# CocoMEMJr_v1_00.net
KiCad netlist of a schematic drawn in EAGLE
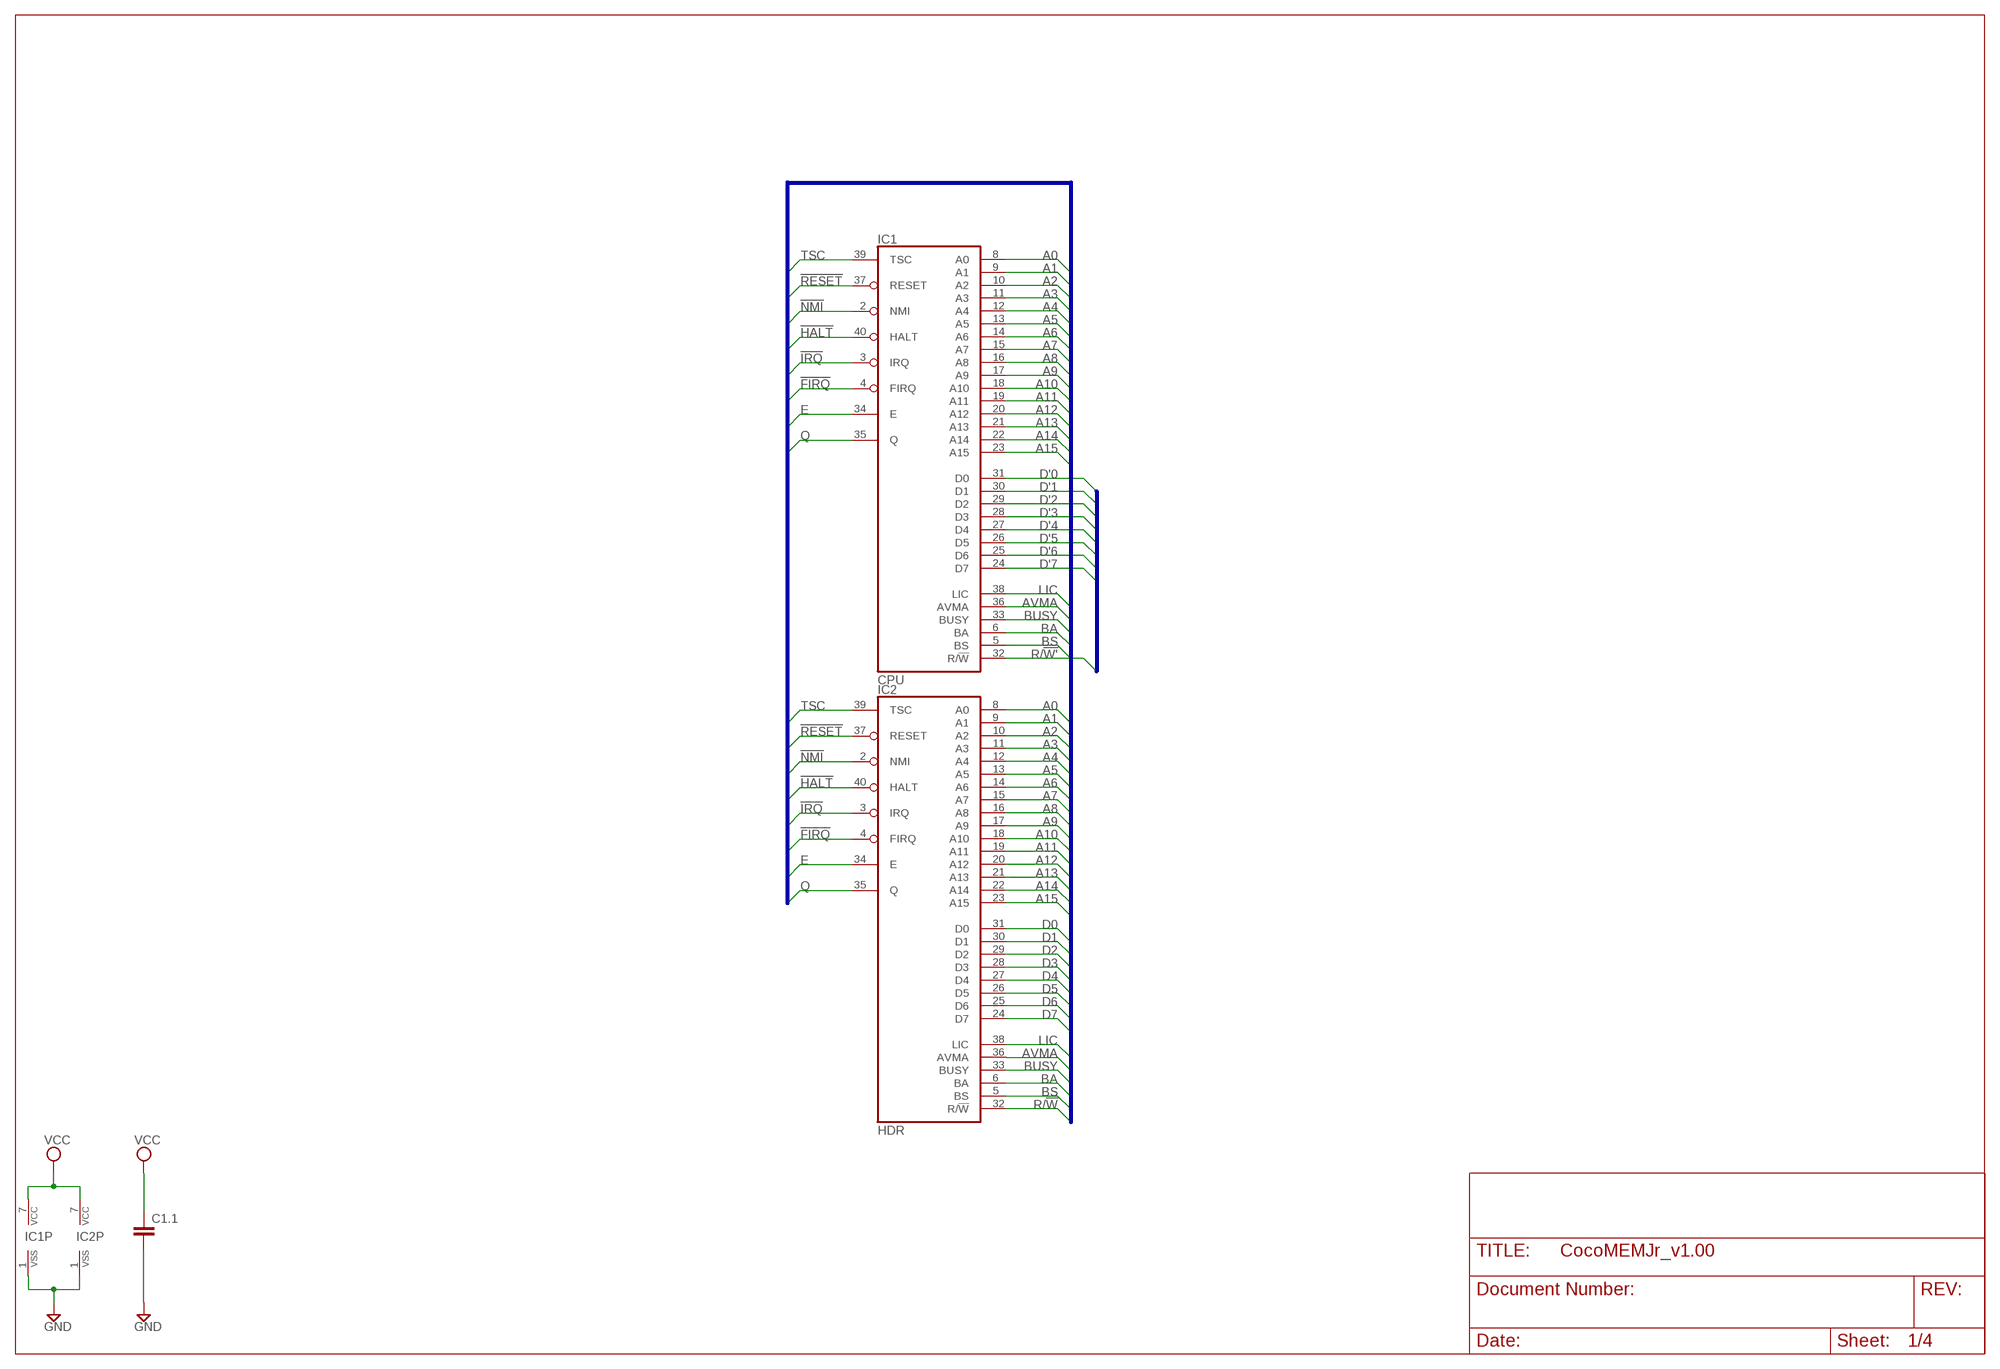
[diagram p0: schematic, sheet 1]
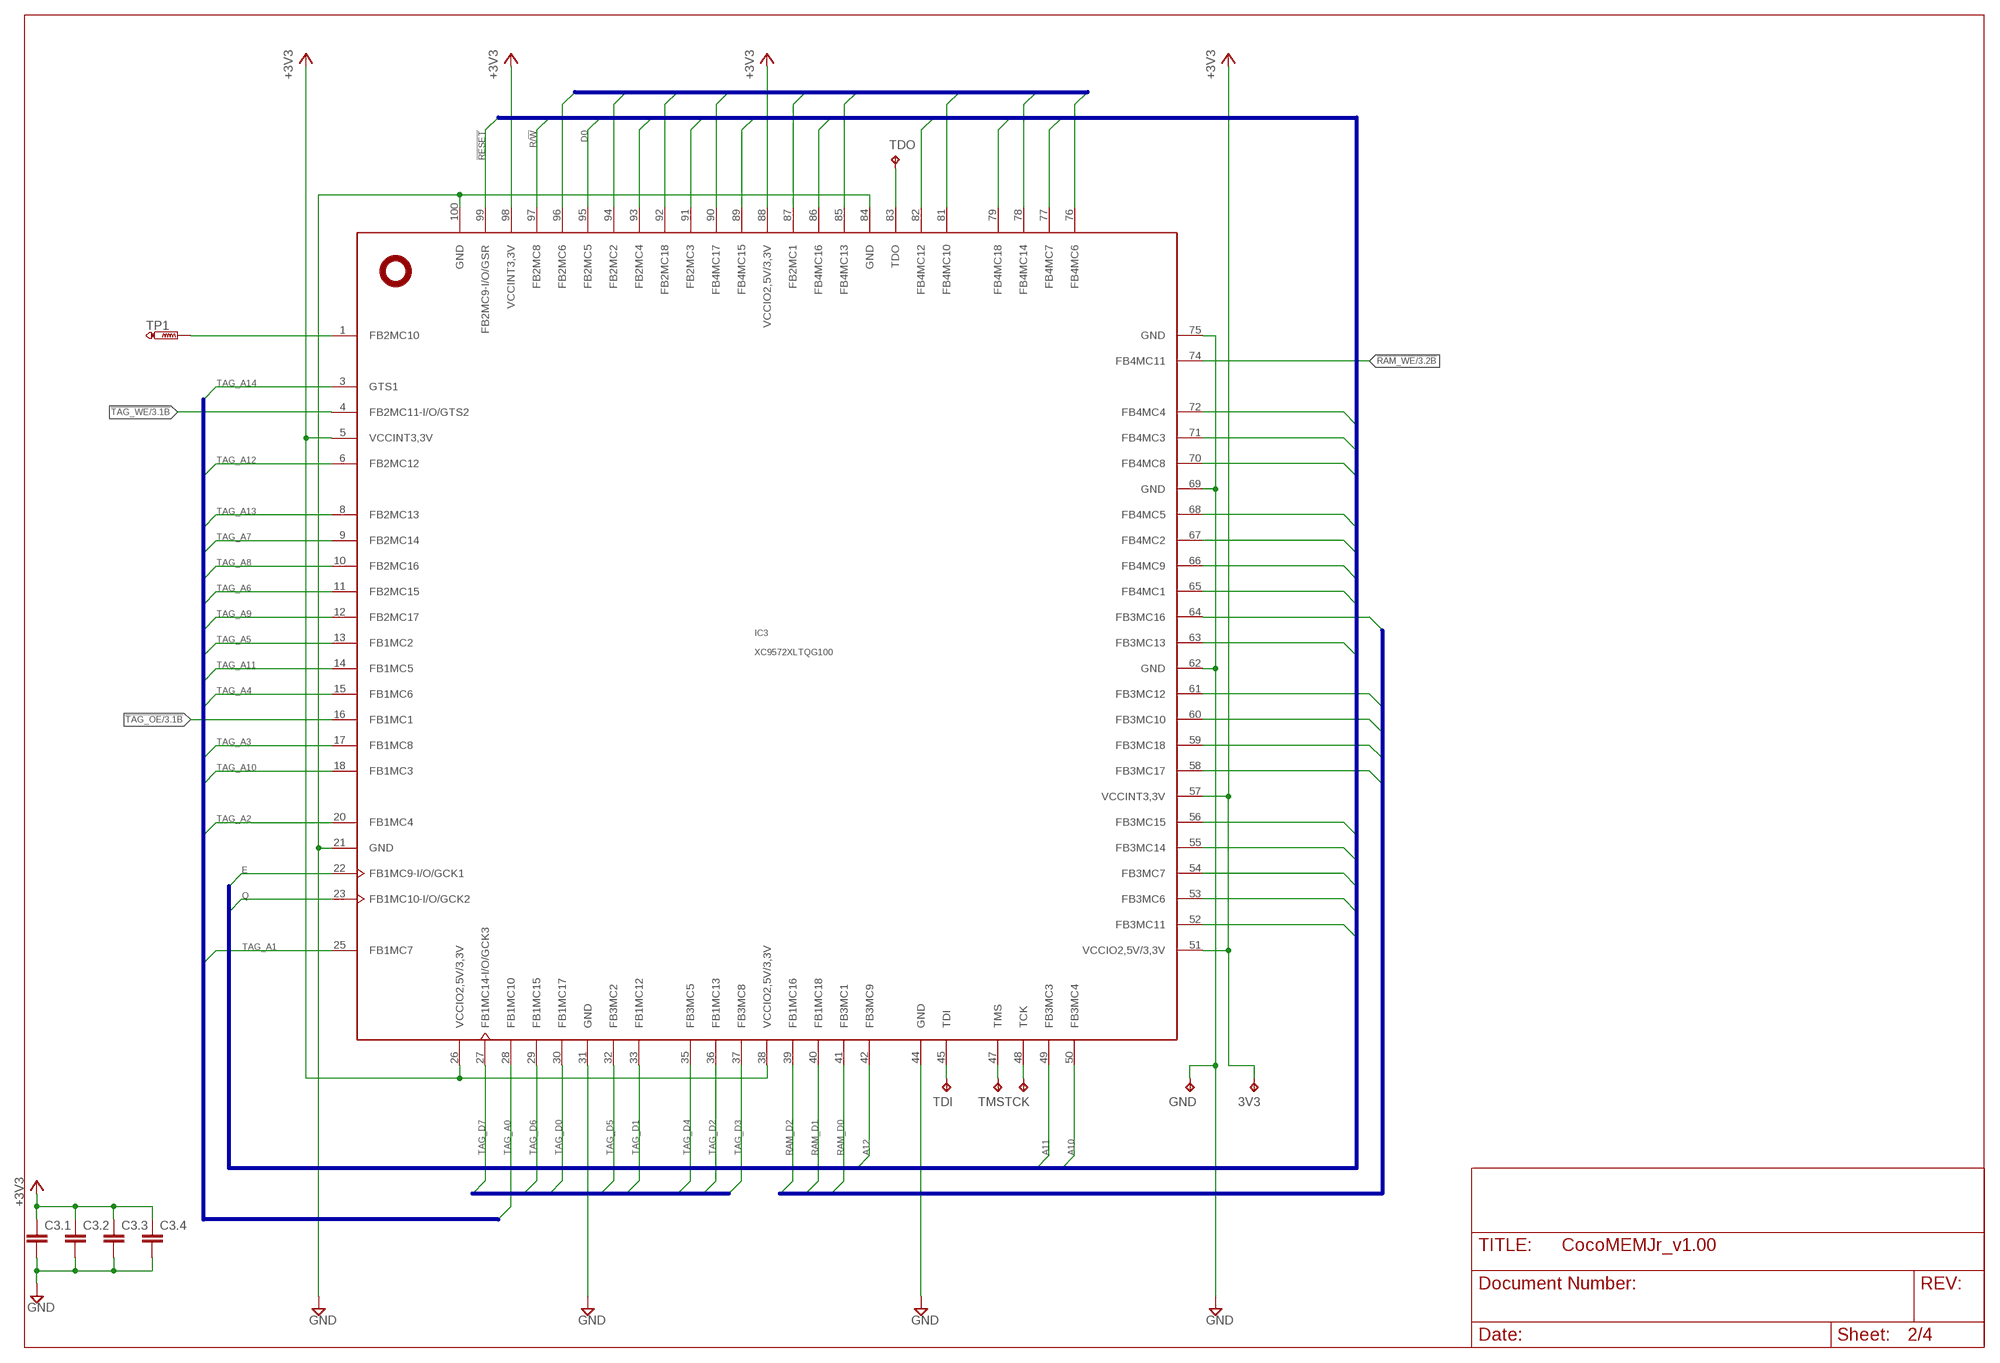
[diagram p1: schematic, sheet 2]
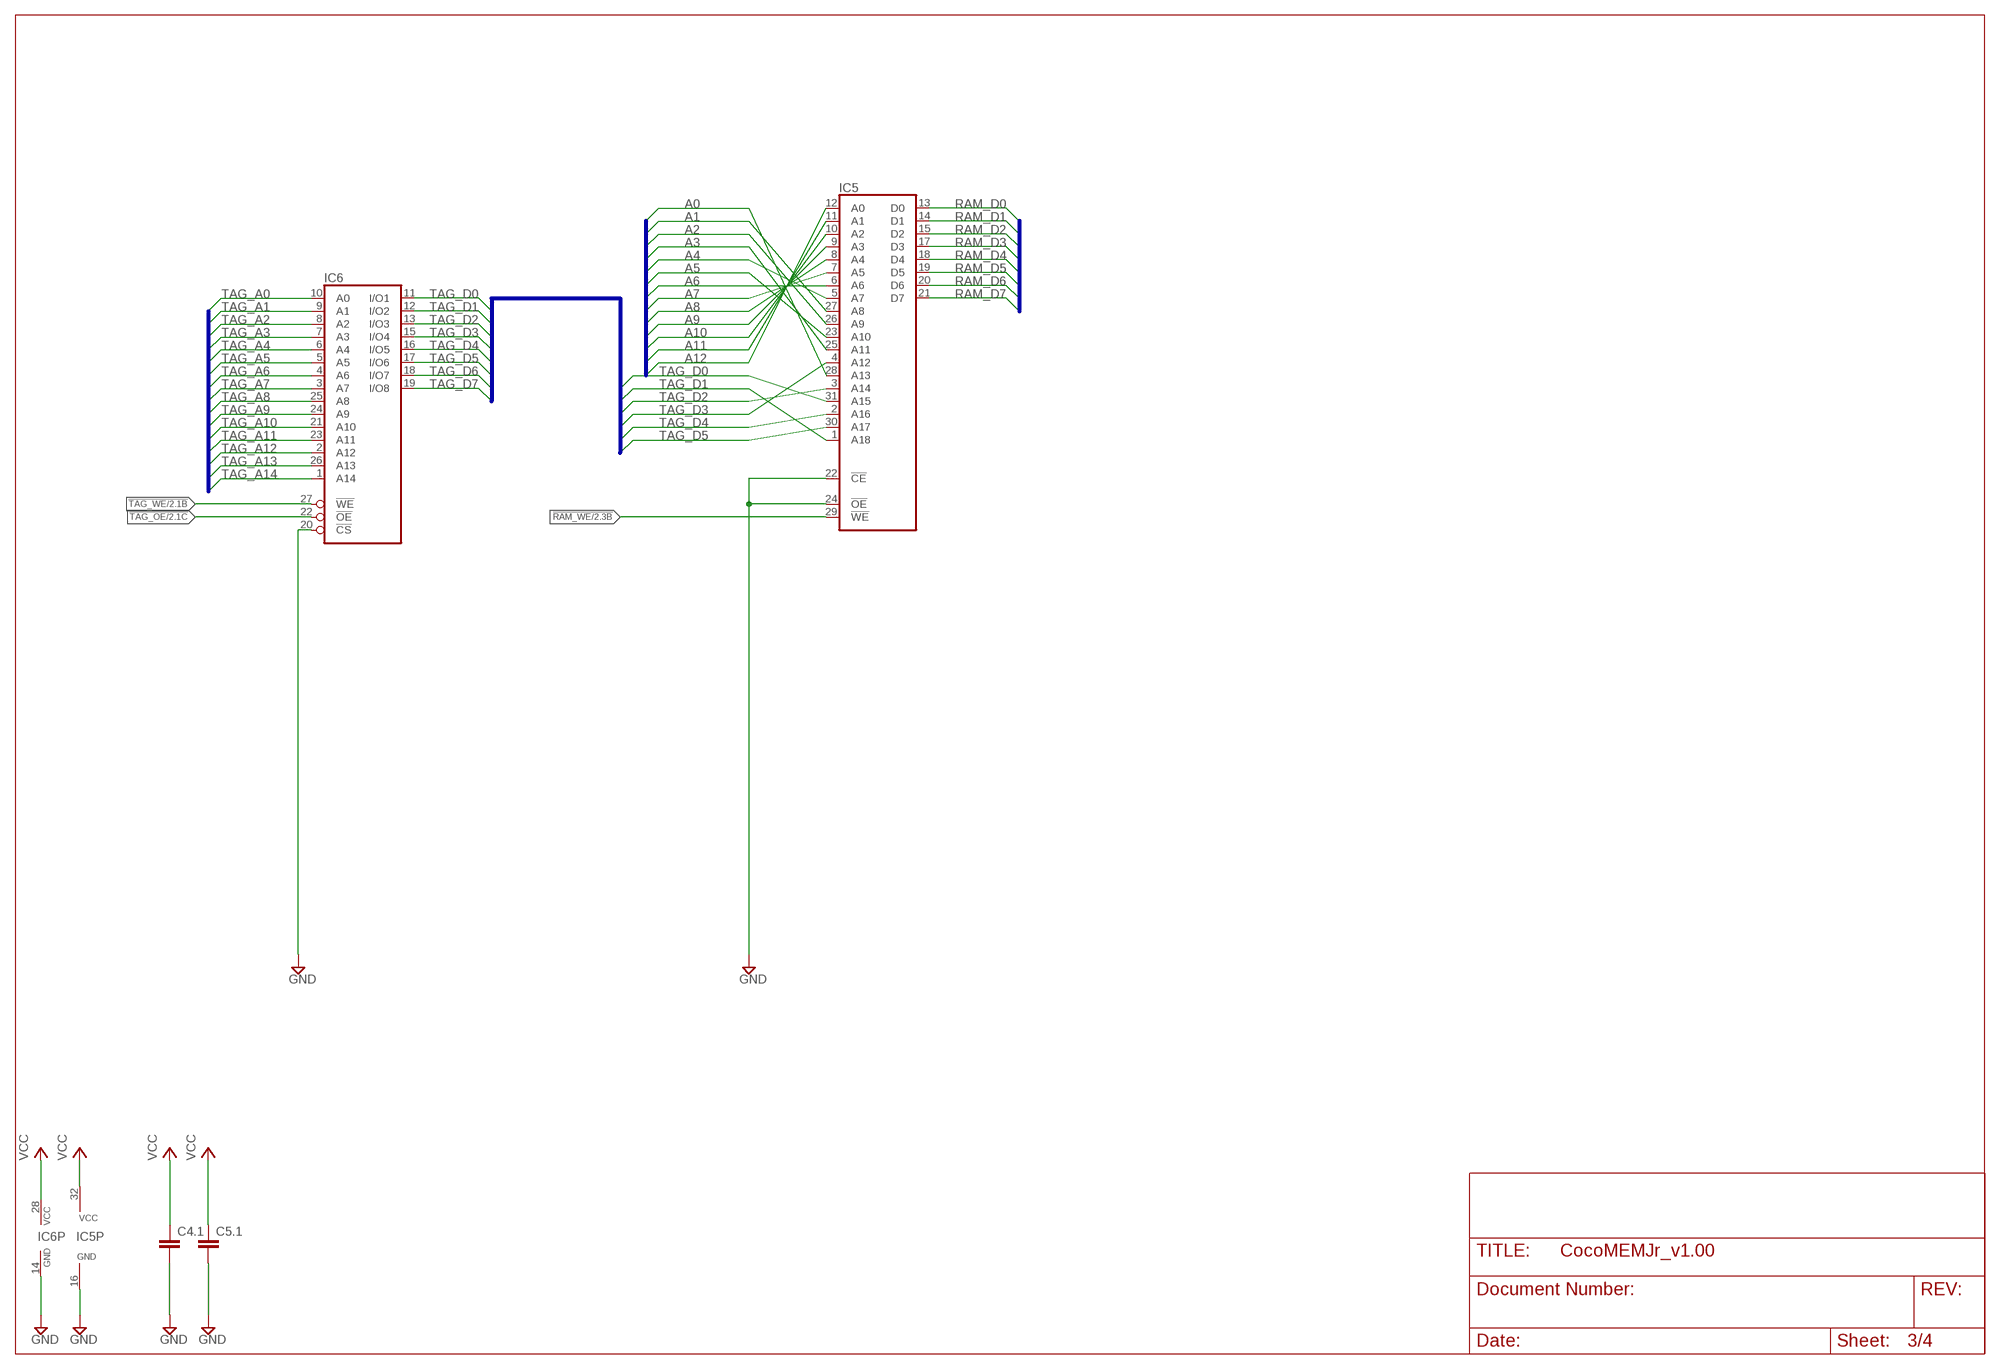
[diagram p2: schematic, sheet 3]
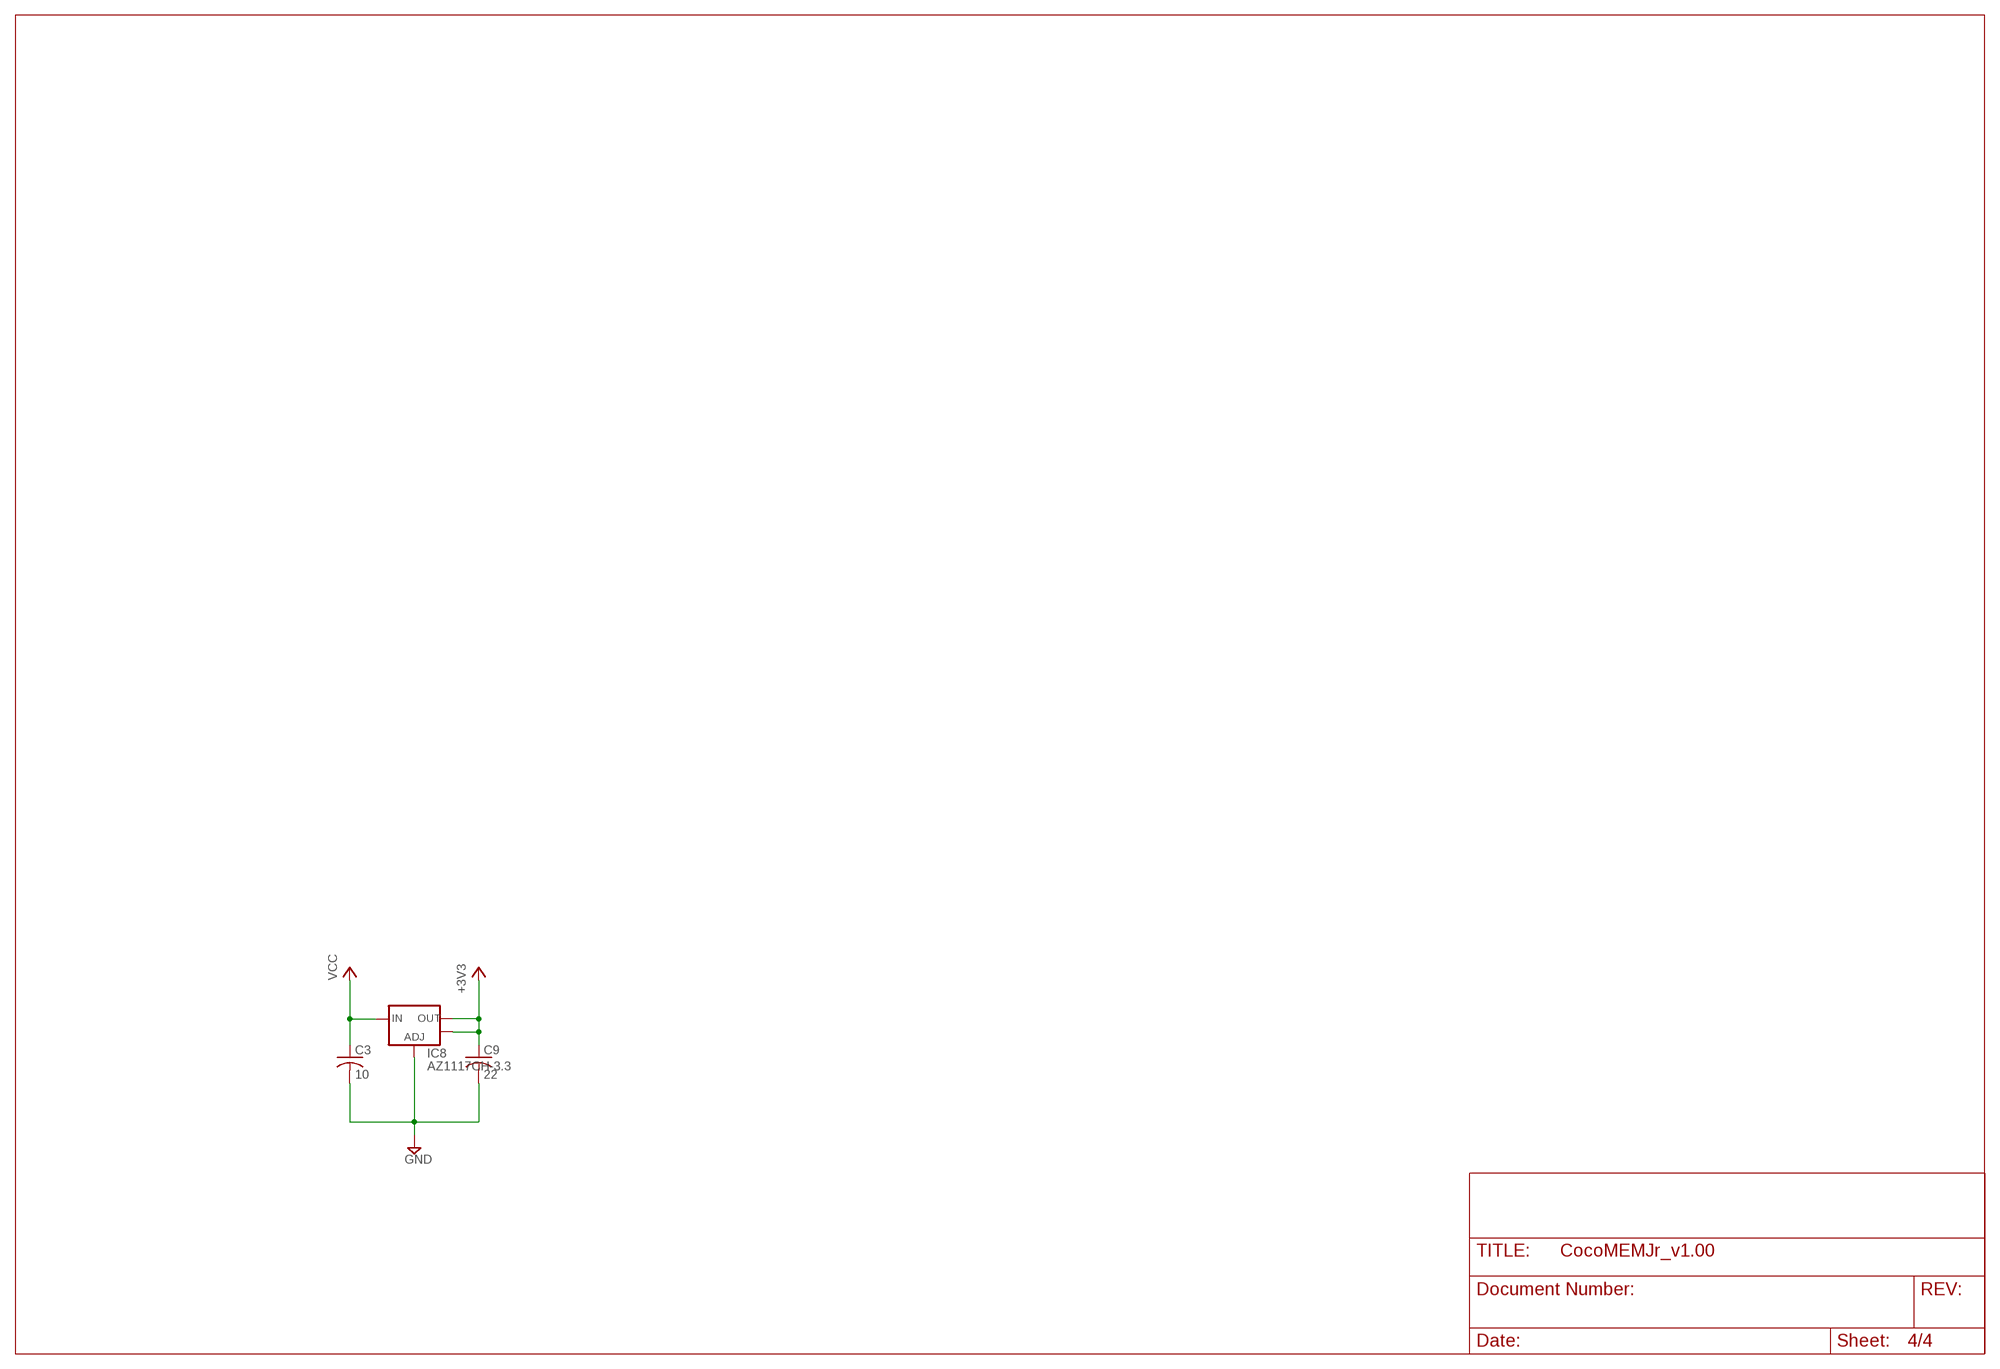
[diagram p3: schematic, sheet 4]

(export (version "E")
  (design (tool "Eeschema 10.0.6"))
  (components
    (comp (ref "C4.1")
      (value "C-EUC0402")
      (footprint "eagle-import:C0402")
      (libsource (lib "eagle-import") (part "C-EUC0402"))
    )
    (comp (ref "C5.1")
      (value "C-EUC0402")
      (footprint "eagle-import:C0402")
      (libsource (lib "eagle-import") (part "C-EUC0402"))
    )
    (comp (ref "IC5")
      (value "AS6C4008PCNR")
      (footprint "eagle-import:DIL32-RP")
      (libsource (lib "eagle-import") (part "AS6C4008PCNR"))
    )
    (comp (ref "IC6")
      (value "71256SAR")
      (footprint "eagle-import:DIL28-3RP")
      (libsource (lib "eagle-import") (part "71256SAR"))
    )
    (comp (ref "C3")
      (value "10")
      (footprint "eagle-import:C0805")
      (libsource (lib "eagle-import") (part "C-USC0805"))
    )
    (comp (ref "C9")
      (value "22")
      (footprint "eagle-import:C0805")
      (libsource (lib "eagle-import") (part "C-USC0805"))
    )
    (comp (ref "IC8")
      (value "AZ1117CH-3.3")
      (footprint "eagle-import:SOT223")
      (libsource (lib "eagle-import") (part "V_REG_LM1117SOT223"))
    )
    (comp (ref "C1.1")
      (value "C-EUC0402")
      (footprint "eagle-import:C0402")
      (libsource (lib "eagle-import") (part "C-EUC0402"))
    )
    (comp (ref "IC1")
      (value "CPU")
      (footprint "eagle-import:DIL40-ROUNDPAD")
      (libsource (lib "eagle-import") (part "MC6809ER"))
    )
    (comp (ref "IC2")
      (value "HDR")
      (footprint "eagle-import:DIL40-ROUNDPAD")
      (libsource (lib "eagle-import") (part "MC6809ER"))
    )
    (comp (ref "3V3")
      (value "TPTP08R")
      (footprint "eagle-import:TP08R")
      (libsource (lib "eagle-import") (part "TPTP08R"))
    )
    (comp (ref "C3.1")
      (value "C-EUC0402")
      (footprint "eagle-import:C0402")
      (libsource (lib "eagle-import") (part "C-EUC0402"))
    )
    (comp (ref "C3.2")
      (value "C-EUC0402")
      (footprint "eagle-import:C0402")
      (libsource (lib "eagle-import") (part "C-EUC0402"))
    )
    (comp (ref "C3.3")
      (value "C-EUC0402")
      (footprint "eagle-import:C0402")
      (libsource (lib "eagle-import") (part "C-EUC0402"))
    )
    (comp (ref "C3.4")
      (value "C-EUC0402")
      (footprint "eagle-import:C0402")
      (libsource (lib "eagle-import") (part "C-EUC0402"))
    )
    (comp (ref "GND")
      (value "TPTP08R")
      (footprint "eagle-import:TP08R")
      (libsource (lib "eagle-import") (part "TPTP08R"))
    )
    (comp (ref "IC3")
      (value "XC9572XLTQG100")
      (footprint "eagle-import:TQFP100")
      (libsource (lib "eagle-import") (part "XC9572XLTQG100"))
    )
    (comp (ref "TCK")
      (value "TPTP08R")
      (footprint "eagle-import:TP08R")
      (libsource (lib "eagle-import") (part "TPTP08R"))
    )
    (comp (ref "TDI")
      (value "TPTP08R")
      (footprint "eagle-import:TP08R")
      (libsource (lib "eagle-import") (part "TPTP08R"))
    )
    (comp (ref "TDO")
      (value "TPTP08R")
      (footprint "eagle-import:TP08R")
      (libsource (lib "eagle-import") (part "TPTP08R"))
    )
    (comp (ref "TMS")
      (value "TPTP08R")
      (footprint "eagle-import:TP08R")
      (libsource (lib "eagle-import") (part "TPTP08R"))
    )
    (comp (ref "TP1")
      (value "PTR1B2,54")
      (footprint "eagle-import:B2,54")
      (libsource (lib "eagle-import") (part "PTR1B2,54"))
    )
  )
  (nets
    (net (code "1") (name "+3V3") (class "Default")
      (node (ref "3V3") (pin "TP") (pinfunction "TP_TP") (pintype "input"))
      (node (ref "C3.1") (pin "1") (pinfunction "1_1") (pintype "passive"))
      (node (ref "C3.2") (pin "1") (pinfunction "1_1") (pintype "passive"))
      (node (ref "C3.3") (pin "1") (pinfunction "1_1") (pintype "passive"))
      (node (ref "C3.4") (pin "1") (pinfunction "1_1") (pintype "passive"))
      (node (ref "C9") (pin "1") (pinfunction "1_1") (pintype "passive"))
      (node (ref "IC3") (pin "26") (pinfunction "VCCIO2,5V/3,3V_26") (pintype "power_in"))
      (node (ref "IC3") (pin "38") (pinfunction "VCCIO2,5V/3,3V_38") (pintype "power_in"))
      (node (ref "IC3") (pin "5") (pinfunction "VCCINT3,3V_5") (pintype "power_in"))
      (node (ref "IC3") (pin "51") (pinfunction "VCCIO2,5V/3,3V_51") (pintype "power_in"))
      (node (ref "IC3") (pin "57") (pinfunction "VCCINT3,3V_57") (pintype "power_in"))
      (node (ref "IC3") (pin "88") (pinfunction "VCCIO2,5V/3,3V_88") (pintype "power_in"))
      (node (ref "IC3") (pin "98") (pinfunction "VCCINT3,3V_98") (pintype "power_in"))
      (node (ref "IC8") (pin "2") (pinfunction "OUT_2") (pintype "output"))
      (node (ref "IC8") (pin "4") (pinfunction "OUT_4") (pintype "output"))
    )
    (net (code "3") (name "A0") (class "Default")
      (node (ref "IC1") (pin "8") (pinfunction "A0_8") (pintype "tri_state"))
      (node (ref "IC2") (pin "8") (pinfunction "A0_8") (pintype "tri_state"))
      (node (ref "IC3") (pin "72") (pinfunction "FB4MC4_72") (pintype "bidirectional"))
      (node (ref "IC5") (pin "28") (pinfunction "A13_28") (pintype "input"))
    )
    (net (code "4") (name "A1") (class "Default")
      (node (ref "IC1") (pin "9") (pinfunction "A1_9") (pintype "tri_state"))
      (node (ref "IC2") (pin "9") (pinfunction "A1_9") (pintype "tri_state"))
      (node (ref "IC3") (pin "71") (pinfunction "FB4MC3_71") (pintype "bidirectional"))
      (node (ref "IC5") (pin "27") (pinfunction "A8_27") (pintype "input"))
    )
    (net (code "5") (name "A2") (class "Default")
      (node (ref "IC1") (pin "10") (pinfunction "A2_10") (pintype "tri_state"))
      (node (ref "IC2") (pin "10") (pinfunction "A2_10") (pintype "tri_state"))
      (node (ref "IC3") (pin "70") (pinfunction "FB4MC8_70") (pintype "bidirectional"))
      (node (ref "IC5") (pin "26") (pinfunction "A9_26") (pintype "input"))
    )
    (net (code "6") (name "A3") (class "Default")
      (node (ref "IC1") (pin "11") (pinfunction "A3_11") (pintype "tri_state"))
      (node (ref "IC2") (pin "11") (pinfunction "A3_11") (pintype "tri_state"))
      (node (ref "IC3") (pin "68") (pinfunction "FB4MC5_68") (pintype "bidirectional"))
      (node (ref "IC5") (pin "25") (pinfunction "A11_25") (pintype "input"))
    )
    (net (code "7") (name "A4") (class "Default")
      (node (ref "IC1") (pin "12") (pinfunction "A4_12") (pintype "tri_state"))
      (node (ref "IC2") (pin "12") (pinfunction "A4_12") (pintype "tri_state"))
      (node (ref "IC3") (pin "52") (pinfunction "FB3MC11_52") (pintype "bidirectional"))
      (node (ref "IC5") (pin "5") (pinfunction "A7_5") (pintype "input"))
    )
    (net (code "8") (name "A5") (class "Default")
      (node (ref "IC1") (pin "13") (pinfunction "A5_13") (pintype "tri_state"))
      (node (ref "IC2") (pin "13") (pinfunction "A5_13") (pintype "tri_state"))
      (node (ref "IC3") (pin "67") (pinfunction "FB4MC2_67") (pintype "bidirectional"))
      (node (ref "IC5") (pin "23") (pinfunction "A10_23") (pintype "input"))
    )
    (net (code "9") (name "A6") (class "Default")
      (node (ref "IC1") (pin "14") (pinfunction "A6_14") (pintype "tri_state"))
      (node (ref "IC2") (pin "14") (pinfunction "A6_14") (pintype "tri_state"))
      (node (ref "IC3") (pin "53") (pinfunction "FB3MC6_53") (pintype "bidirectional"))
      (node (ref "IC5") (pin "6") (pinfunction "A6_6") (pintype "input"))
    )
    (net (code "10") (name "A7") (class "Default")
      (node (ref "IC1") (pin "15") (pinfunction "A7_15") (pintype "tri_state"))
      (node (ref "IC2") (pin "15") (pinfunction "A7_15") (pintype "tri_state"))
      (node (ref "IC3") (pin "54") (pinfunction "FB3MC7_54") (pintype "bidirectional"))
      (node (ref "IC5") (pin "7") (pinfunction "A5_7") (pintype "input"))
    )
    (net (code "11") (name "A8") (class "Default")
      (node (ref "IC1") (pin "16") (pinfunction "A8_16") (pintype "tri_state"))
      (node (ref "IC2") (pin "16") (pinfunction "A8_16") (pintype "tri_state"))
      (node (ref "IC3") (pin "55") (pinfunction "FB3MC14_55") (pintype "bidirectional"))
      (node (ref "IC5") (pin "8") (pinfunction "A4_8") (pintype "input"))
    )
    (net (code "12") (name "A9") (class "Default")
      (node (ref "IC1") (pin "17") (pinfunction "A9_17") (pintype "tri_state"))
      (node (ref "IC2") (pin "17") (pinfunction "A9_17") (pintype "tri_state"))
      (node (ref "IC3") (pin "56") (pinfunction "FB3MC15_56") (pintype "bidirectional"))
      (node (ref "IC5") (pin "9") (pinfunction "A3_9") (pintype "input"))
    )
    (net (code "13") (name "A10") (class "Default")
      (node (ref "IC1") (pin "18") (pinfunction "A10_18") (pintype "tri_state"))
      (node (ref "IC2") (pin "18") (pinfunction "A10_18") (pintype "tri_state"))
      (node (ref "IC3") (pin "50") (pinfunction "FB3MC4_50") (pintype "bidirectional"))
      (node (ref "IC5") (pin "10") (pinfunction "A2_10") (pintype "input"))
    )
    (net (code "14") (name "A11") (class "Default")
      (node (ref "IC1") (pin "19") (pinfunction "A11_19") (pintype "tri_state"))
      (node (ref "IC2") (pin "19") (pinfunction "A11_19") (pintype "tri_state"))
      (node (ref "IC3") (pin "49") (pinfunction "FB3MC3_49") (pintype "bidirectional"))
      (node (ref "IC5") (pin "11") (pinfunction "A1_11") (pintype "input"))
    )
    (net (code "15") (name "A12") (class "Default")
      (node (ref "IC1") (pin "20") (pinfunction "A12_20") (pintype "tri_state"))
      (node (ref "IC2") (pin "20") (pinfunction "A12_20") (pintype "tri_state"))
      (node (ref "IC3") (pin "42") (pinfunction "FB3MC9_42") (pintype "bidirectional"))
      (node (ref "IC5") (pin "12") (pinfunction "A0_12") (pintype "input"))
    )
    (net (code "16") (name "A13") (class "Default")
      (node (ref "IC1") (pin "21") (pinfunction "A13_21") (pintype "tri_state"))
      (node (ref "IC2") (pin "21") (pinfunction "A13_21") (pintype "tri_state"))
      (node (ref "IC3") (pin "63") (pinfunction "FB3MC13_63") (pintype "bidirectional"))
    )
    (net (code "17") (name "A14") (class "Default")
      (node (ref "IC1") (pin "22") (pinfunction "A14_22") (pintype "tri_state"))
      (node (ref "IC2") (pin "22") (pinfunction "A14_22") (pintype "tri_state"))
      (node (ref "IC3") (pin "65") (pinfunction "FB4MC1_65") (pintype "bidirectional"))
    )
    (net (code "18") (name "A15") (class "Default")
      (node (ref "IC1") (pin "23") (pinfunction "A15_23") (pintype "tri_state"))
      (node (ref "IC2") (pin "23") (pinfunction "A15_23") (pintype "tri_state"))
      (node (ref "IC3") (pin "66") (pinfunction "FB4MC9_66") (pintype "bidirectional"))
    )
    (net (code "19") (name "AVMA") (class "Default")
      (node (ref "IC1") (pin "36") (pinfunction "AVMA_36") (pintype "output"))
      (node (ref "IC2") (pin "36") (pinfunction "AVMA_36") (pintype "output"))
    )
    (net (code "20") (name "BA") (class "Default")
      (node (ref "IC1") (pin "6") (pinfunction "BA_6") (pintype "output"))
      (node (ref "IC2") (pin "6") (pinfunction "BA_6") (pintype "output"))
    )
    (net (code "21") (name "BS") (class "Default")
      (node (ref "IC1") (pin "5") (pinfunction "BS_5") (pintype "output"))
      (node (ref "IC2") (pin "5") (pinfunction "BS_5") (pintype "output"))
    )
    (net (code "22") (name "BUSY") (class "Default")
      (node (ref "IC1") (pin "33") (pinfunction "BUSY_33") (pintype "output"))
      (node (ref "IC2") (pin "33") (pinfunction "BUSY_33") (pintype "output"))
    )
    (net (code "23") (name "D'0") (class "Default")
      (node (ref "IC1") (pin "31") (pinfunction "D0_31") (pintype "bidirectional"))
      (node (ref "IC3") (pin "94") (pinfunction "FB2MC2_94") (pintype "bidirectional"))
    )
    (net (code "24") (name "D'1") (class "Default")
      (node (ref "IC1") (pin "30") (pinfunction "D1_30") (pintype "bidirectional"))
      (node (ref "IC3") (pin "92") (pinfunction "FB2MC18_92") (pintype "bidirectional"))
    )
    (net (code "25") (name "D'2") (class "Default")
      (node (ref "IC1") (pin "29") (pinfunction "D2_29") (pintype "bidirectional"))
      (node (ref "IC3") (pin "90") (pinfunction "FB4MC17_90") (pintype "bidirectional"))
    )
    (net (code "26") (name "D'3") (class "Default")
      (node (ref "IC1") (pin "28") (pinfunction "D3_28") (pintype "bidirectional"))
      (node (ref "IC3") (pin "87") (pinfunction "FB2MC1_87") (pintype "bidirectional"))
    )
    (net (code "27") (name "D'4") (class "Default")
      (node (ref "IC1") (pin "27") (pinfunction "D4_27") (pintype "bidirectional"))
      (node (ref "IC3") (pin "85") (pinfunction "FB4MC13_85") (pintype "bidirectional"))
    )
    (net (code "28") (name "D'5") (class "Default")
      (node (ref "IC1") (pin "26") (pinfunction "D5_26") (pintype "bidirectional"))
      (node (ref "IC3") (pin "81") (pinfunction "FB4MC10_81") (pintype "bidirectional"))
    )
    (net (code "29") (name "D'6") (class "Default")
      (node (ref "IC1") (pin "25") (pinfunction "D6_25") (pintype "bidirectional"))
      (node (ref "IC3") (pin "78") (pinfunction "FB4MC14_78") (pintype "bidirectional"))
    )
    (net (code "30") (name "D'7") (class "Default")
      (node (ref "IC1") (pin "24") (pinfunction "D7_24") (pintype "bidirectional"))
      (node (ref "IC3") (pin "76") (pinfunction "FB4MC6_76") (pintype "bidirectional"))
    )
    (net (code "31") (name "D0") (class "Default")
      (node (ref "IC2") (pin "31") (pinfunction "D0_31") (pintype "bidirectional"))
      (node (ref "IC3") (pin "95") (pinfunction "FB2MC5_95") (pintype "bidirectional"))
    )
    (net (code "32") (name "D1") (class "Default")
      (node (ref "IC2") (pin "30") (pinfunction "D1_30") (pintype "bidirectional"))
      (node (ref "IC3") (pin "93") (pinfunction "FB2MC4_93") (pintype "bidirectional"))
    )
    (net (code "33") (name "D2") (class "Default")
      (node (ref "IC2") (pin "29") (pinfunction "D2_29") (pintype "bidirectional"))
      (node (ref "IC3") (pin "91") (pinfunction "FB2MC3_91") (pintype "bidirectional"))
    )
    (net (code "34") (name "D3") (class "Default")
      (node (ref "IC2") (pin "28") (pinfunction "D3_28") (pintype "bidirectional"))
      (node (ref "IC3") (pin "89") (pinfunction "FB4MC15_89") (pintype "bidirectional"))
    )
    (net (code "35") (name "D4") (class "Default")
      (node (ref "IC2") (pin "27") (pinfunction "D4_27") (pintype "bidirectional"))
      (node (ref "IC3") (pin "86") (pinfunction "FB4MC16_86") (pintype "bidirectional"))
    )
    (net (code "36") (name "D5") (class "Default")
      (node (ref "IC2") (pin "26") (pinfunction "D5_26") (pintype "bidirectional"))
      (node (ref "IC3") (pin "82") (pinfunction "FB4MC12_82") (pintype "bidirectional"))
    )
    (net (code "37") (name "D6") (class "Default")
      (node (ref "IC2") (pin "25") (pinfunction "D6_25") (pintype "bidirectional"))
      (node (ref "IC3") (pin "79") (pinfunction "FB4MC18_79") (pintype "bidirectional"))
    )
    (net (code "38") (name "D7") (class "Default")
      (node (ref "IC2") (pin "24") (pinfunction "D7_24") (pintype "bidirectional"))
      (node (ref "IC3") (pin "77") (pinfunction "FB4MC7_77") (pintype "bidirectional"))
    )
    (net (code "39") (name "E") (class "Default")
      (node (ref "IC1") (pin "34") (pinfunction "E_34") (pintype "input"))
      (node (ref "IC2") (pin "34") (pinfunction "E_34") (pintype "input"))
      (node (ref "IC3") (pin "22") (pinfunction "FB1MC9-I/O/GCK1_22") (pintype "bidirectional"))
    )
    (net (code "40") (name "GND") (class "Default")
      (node (ref "C1.1") (pin "2") (pinfunction "2_2") (pintype "passive"))
      (node (ref "C3") (pin "2") (pinfunction "2_2") (pintype "passive"))
      (node (ref "C3.1") (pin "2") (pinfunction "2_2") (pintype "passive"))
      (node (ref "C3.2") (pin "2") (pinfunction "2_2") (pintype "passive"))
      (node (ref "C3.3") (pin "2") (pinfunction "2_2") (pintype "passive"))
      (node (ref "C3.4") (pin "2") (pinfunction "2_2") (pintype "passive"))
      (node (ref "C4.1") (pin "2") (pinfunction "2_2") (pintype "passive"))
      (node (ref "C5.1") (pin "2") (pinfunction "2_2") (pintype "passive"))
      (node (ref "C9") (pin "2") (pinfunction "2_2") (pintype "passive"))
      (node (ref "GND") (pin "TP") (pinfunction "TP_TP") (pintype "input"))
      (node (ref "IC1") (pin "1") (pinfunction "VSS_1") (pintype "power_in"))
      (node (ref "IC2") (pin "1") (pinfunction "VSS_1") (pintype "power_in"))
      (node (ref "IC3") (pin "100") (pinfunction "GND_100") (pintype "power_in"))
      (node (ref "IC3") (pin "21") (pinfunction "GND_21") (pintype "power_in"))
      (node (ref "IC3") (pin "31") (pinfunction "GND_31") (pintype "power_in"))
      (node (ref "IC3") (pin "44") (pinfunction "GND_44") (pintype "power_in"))
      (node (ref "IC3") (pin "62") (pinfunction "GND_62") (pintype "power_in"))
      (node (ref "IC3") (pin "69") (pinfunction "GND_69") (pintype "power_in"))
      (node (ref "IC3") (pin "75") (pinfunction "GND_75") (pintype "power_in"))
      (node (ref "IC3") (pin "84") (pinfunction "GND_84") (pintype "power_in"))
      (node (ref "IC5") (pin "16") (pinfunction "GND_16") (pintype "power_in"))
      (node (ref "IC5") (pin "22") (pinfunction "~{CE}_22") (pintype "input"))
      (node (ref "IC5") (pin "24") (pinfunction "~{OE}_24") (pintype "input"))
      (node (ref "IC6") (pin "14") (pinfunction "GND_14") (pintype "power_in"))
      (node (ref "IC6") (pin "20") (pinfunction "~{CS}_20") (pintype "input"))
      (node (ref "IC8") (pin "1") (pinfunction "ADJ_1") (pintype "input"))
    )
    (net (code "41") (name "LIC") (class "Default")
      (node (ref "IC1") (pin "38") (pinfunction "LIC_38") (pintype "output"))
      (node (ref "IC2") (pin "38") (pinfunction "LIC_38") (pintype "output"))
    )
    (net (code "42") (name "Net-(IC3-FB2MC10)") (class "Default")
      (node (ref "IC3") (pin "1") (pinfunction "FB2MC10_1") (pintype "bidirectional"))
      (node (ref "TP1") (pin "TP") (pinfunction "TP_TP") (pintype "input"))
    )
    (net (code "43") (name "Net-(IC3-TCK)") (class "Default")
      (node (ref "IC3") (pin "48") (pinfunction "TCK_48") (pintype "bidirectional"))
      (node (ref "TCK") (pin "TP") (pinfunction "TP_TP") (pintype "input"))
    )
    (net (code "44") (name "Net-(IC3-TDI)") (class "Default")
      (node (ref "IC3") (pin "45") (pinfunction "TDI_45") (pintype "bidirectional"))
      (node (ref "TDI") (pin "TP") (pinfunction "TP_TP") (pintype "input"))
    )
    (net (code "45") (name "Net-(IC3-TDO)") (class "Default")
      (node (ref "IC3") (pin "83") (pinfunction "TDO_83") (pintype "bidirectional"))
      (node (ref "TDO") (pin "TP") (pinfunction "TP_TP") (pintype "input"))
    )
    (net (code "46") (name "Net-(IC3-TMS)") (class "Default")
      (node (ref "IC3") (pin "47") (pinfunction "TMS_47") (pintype "bidirectional"))
      (node (ref "TMS") (pin "TP") (pinfunction "TP_TP") (pintype "input"))
    )
    (net (code "47") (name "Q") (class "Default")
      (node (ref "IC1") (pin "35") (pinfunction "Q_35") (pintype "input"))
      (node (ref "IC2") (pin "35") (pinfunction "Q_35") (pintype "input"))
      (node (ref "IC3") (pin "23") (pinfunction "FB1MC10-I/O/GCK2_23") (pintype "bidirectional"))
    )
    (net (code "48") (name "RAM_D0") (class "Default")
      (node (ref "IC3") (pin "41") (pinfunction "FB3MC1_41") (pintype "bidirectional"))
      (node (ref "IC5") (pin "13") (pinfunction "D0_13") (pintype "bidirectional"))
    )
    (net (code "49") (name "RAM_D1") (class "Default")
      (node (ref "IC3") (pin "40") (pinfunction "FB1MC18_40") (pintype "bidirectional"))
      (node (ref "IC5") (pin "14") (pinfunction "D1_14") (pintype "bidirectional"))
    )
    (net (code "50") (name "RAM_D2") (class "Default")
      (node (ref "IC3") (pin "39") (pinfunction "FB1MC16_39") (pintype "bidirectional"))
      (node (ref "IC5") (pin "15") (pinfunction "D2_15") (pintype "bidirectional"))
    )
    (net (code "51") (name "RAM_D3") (class "Default")
      (node (ref "IC3") (pin "58") (pinfunction "FB3MC17_58") (pintype "bidirectional"))
      (node (ref "IC5") (pin "17") (pinfunction "D3_17") (pintype "bidirectional"))
    )
    (net (code "52") (name "RAM_D4") (class "Default")
      (node (ref "IC3") (pin "59") (pinfunction "FB3MC18_59") (pintype "bidirectional"))
      (node (ref "IC5") (pin "18") (pinfunction "D4_18") (pintype "bidirectional"))
    )
    (net (code "53") (name "RAM_D5") (class "Default")
      (node (ref "IC3") (pin "60") (pinfunction "FB3MC10_60") (pintype "bidirectional"))
      (node (ref "IC5") (pin "19") (pinfunction "D5_19") (pintype "bidirectional"))
    )
    (net (code "54") (name "RAM_D6") (class "Default")
      (node (ref "IC3") (pin "61") (pinfunction "FB3MC12_61") (pintype "bidirectional"))
      (node (ref "IC5") (pin "20") (pinfunction "D6_20") (pintype "bidirectional"))
    )
    (net (code "55") (name "RAM_D7") (class "Default")
      (node (ref "IC3") (pin "64") (pinfunction "FB3MC16_64") (pintype "bidirectional"))
      (node (ref "IC5") (pin "21") (pinfunction "D7_21") (pintype "bidirectional"))
    )
    (net (code "56") (name "R{slash}~{W'}") (class "Default")
      (node (ref "IC1") (pin "32") (pinfunction "R/~{W}_32") (pintype "output"))
      (node (ref "IC3") (pin "96") (pinfunction "FB2MC6_96") (pintype "bidirectional"))
    )
    (net (code "57") (name "R{slash}~{W}") (class "Default")
      (node (ref "IC2") (pin "32") (pinfunction "R/~{W}_32") (pintype "output"))
      (node (ref "IC3") (pin "97") (pinfunction "FB2MC8_97") (pintype "bidirectional"))
    )
    (net (code "58") (name "TAG_A0") (class "Default")
      (node (ref "IC3") (pin "28") (pinfunction "FB1MC10_28") (pintype "bidirectional"))
      (node (ref "IC6") (pin "10") (pinfunction "A0_10") (pintype "input"))
    )
    (net (code "59") (name "TAG_A1") (class "Default")
      (node (ref "IC3") (pin "25") (pinfunction "FB1MC7_25") (pintype "bidirectional"))
      (node (ref "IC6") (pin "9") (pinfunction "A1_9") (pintype "input"))
    )
    (net (code "60") (name "TAG_A2") (class "Default")
      (node (ref "IC3") (pin "20") (pinfunction "FB1MC4_20") (pintype "bidirectional"))
      (node (ref "IC6") (pin "8") (pinfunction "A2_8") (pintype "input"))
    )
    (net (code "61") (name "TAG_A3") (class "Default")
      (node (ref "IC3") (pin "17") (pinfunction "FB1MC8_17") (pintype "bidirectional"))
      (node (ref "IC6") (pin "7") (pinfunction "A3_7") (pintype "input"))
    )
    (net (code "62") (name "TAG_A4") (class "Default")
      (node (ref "IC3") (pin "15") (pinfunction "FB1MC6_15") (pintype "bidirectional"))
      (node (ref "IC6") (pin "6") (pinfunction "A4_6") (pintype "input"))
    )
    (net (code "63") (name "TAG_A5") (class "Default")
      (node (ref "IC3") (pin "13") (pinfunction "FB1MC2_13") (pintype "bidirectional"))
      (node (ref "IC6") (pin "5") (pinfunction "A5_5") (pintype "input"))
    )
    (net (code "64") (name "TAG_A6") (class "Default")
      (node (ref "IC3") (pin "11") (pinfunction "FB2MC15_11") (pintype "bidirectional"))
      (node (ref "IC6") (pin "4") (pinfunction "A6_4") (pintype "input"))
    )
    (net (code "65") (name "TAG_A7") (class "Default")
      (node (ref "IC3") (pin "9") (pinfunction "FB2MC14_9") (pintype "bidirectional"))
      (node (ref "IC6") (pin "3") (pinfunction "A7_3") (pintype "input"))
    )
    (net (code "66") (name "TAG_A8") (class "Default")
      (node (ref "IC3") (pin "10") (pinfunction "FB2MC16_10") (pintype "bidirectional"))
      (node (ref "IC6") (pin "25") (pinfunction "A8_25") (pintype "input"))
    )
    (net (code "67") (name "TAG_A9") (class "Default")
      (node (ref "IC3") (pin "12") (pinfunction "FB2MC17_12") (pintype "bidirectional"))
      (node (ref "IC6") (pin "24") (pinfunction "A9_24") (pintype "input"))
    )
    (net (code "68") (name "TAG_A10") (class "Default")
      (node (ref "IC3") (pin "18") (pinfunction "FB1MC3_18") (pintype "bidirectional"))
      (node (ref "IC6") (pin "21") (pinfunction "A10_21") (pintype "input"))
    )
    (net (code "69") (name "TAG_A11") (class "Default")
      (node (ref "IC3") (pin "14") (pinfunction "FB1MC5_14") (pintype "bidirectional"))
      (node (ref "IC6") (pin "23") (pinfunction "A11_23") (pintype "input"))
    )
    (net (code "70") (name "TAG_A12") (class "Default")
      (node (ref "IC3") (pin "6") (pinfunction "FB2MC12_6") (pintype "bidirectional"))
      (node (ref "IC6") (pin "2") (pinfunction "A12_2") (pintype "input"))
    )
    (net (code "71") (name "TAG_A13") (class "Default")
      (node (ref "IC3") (pin "8") (pinfunction "FB2MC13_8") (pintype "bidirectional"))
      (node (ref "IC6") (pin "26") (pinfunction "A13_26") (pintype "input"))
    )
    (net (code "72") (name "TAG_A14") (class "Default")
      (node (ref "IC3") (pin "3") (pinfunction "GTS1_3") (pintype "bidirectional"))
      (node (ref "IC6") (pin "1") (pinfunction "A14_1") (pintype "input"))
    )
    (net (code "73") (name "TAG_D0") (class "Default")
      (node (ref "IC3") (pin "30") (pinfunction "FB1MC17_30") (pintype "bidirectional"))
      (node (ref "IC5") (pin "31") (pinfunction "A15_31") (pintype "input"))
      (node (ref "IC6") (pin "11") (pinfunction "I/O1_11") (pintype "bidirectional"))
    )
    (net (code "74") (name "TAG_D1") (class "Default")
      (node (ref "IC3") (pin "33") (pinfunction "FB1MC12_33") (pintype "bidirectional"))
      (node (ref "IC5") (pin "1") (pinfunction "A18_1") (pintype "input"))
      (node (ref "IC6") (pin "12") (pinfunction "I/O2_12") (pintype "bidirectional"))
    )
    (net (code "75") (name "TAG_D2") (class "Default")
      (node (ref "IC3") (pin "36") (pinfunction "FB1MC13_36") (pintype "bidirectional"))
      (node (ref "IC5") (pin "3") (pinfunction "A14_3") (pintype "input"))
      (node (ref "IC6") (pin "13") (pinfunction "I/O3_13") (pintype "bidirectional"))
    )
    (net (code "76") (name "TAG_D3") (class "Default")
      (node (ref "IC3") (pin "37") (pinfunction "FB3MC8_37") (pintype "bidirectional"))
      (node (ref "IC5") (pin "4") (pinfunction "A12_4") (pintype "input"))
      (node (ref "IC6") (pin "15") (pinfunction "I/O4_15") (pintype "bidirectional"))
    )
    (net (code "77") (name "TAG_D4") (class "Default")
      (node (ref "IC3") (pin "35") (pinfunction "FB3MC5_35") (pintype "bidirectional"))
      (node (ref "IC5") (pin "2") (pinfunction "A16_2") (pintype "input"))
      (node (ref "IC6") (pin "16") (pinfunction "I/O5_16") (pintype "bidirectional"))
    )
    (net (code "78") (name "TAG_D5") (class "Default")
      (node (ref "IC3") (pin "32") (pinfunction "FB3MC2_32") (pintype "bidirectional"))
      (node (ref "IC5") (pin "30") (pinfunction "A17_30") (pintype "input"))
      (node (ref "IC6") (pin "17") (pinfunction "I/O6_17") (pintype "bidirectional"))
    )
    (net (code "79") (name "TAG_D6") (class "Default")
      (node (ref "IC3") (pin "29") (pinfunction "FB1MC15_29") (pintype "bidirectional"))
      (node (ref "IC6") (pin "18") (pinfunction "I/O7_18") (pintype "bidirectional"))
    )
    (net (code "80") (name "TAG_D7") (class "Default")
      (node (ref "IC3") (pin "27") (pinfunction "FB1MC14-I/O/GCK3_27") (pintype "bidirectional"))
      (node (ref "IC6") (pin "19") (pinfunction "I/O8_19") (pintype "bidirectional"))
    )
    (net (code "81") (name "TSC") (class "Default")
      (node (ref "IC1") (pin "39") (pinfunction "TSC_39") (pintype "input"))
      (node (ref "IC2") (pin "39") (pinfunction "TSC_39") (pintype "input"))
    )
    (net (code "82") (name "VCC") (class "Default")
      (node (ref "C1.1") (pin "1") (pinfunction "1_1") (pintype "passive"))
      (node (ref "C3") (pin "1") (pinfunction "1_1") (pintype "passive"))
      (node (ref "C4.1") (pin "1") (pinfunction "1_1") (pintype "passive"))
      (node (ref "C5.1") (pin "1") (pinfunction "1_1") (pintype "passive"))
      (node (ref "IC1") (pin "7") (pinfunction "VCC_7") (pintype "power_in"))
      (node (ref "IC2") (pin "7") (pinfunction "VCC_7") (pintype "power_in"))
      (node (ref "IC5") (pin "32") (pinfunction "VCC_32") (pintype "power_in"))
      (node (ref "IC6") (pin "28") (pinfunction "VCC_28") (pintype "power_in"))
      (node (ref "IC8") (pin "3") (pinfunction "IN_3") (pintype "input"))
    )
    (net (code "83") (name "~{FIRQ}") (class "Default")
      (node (ref "IC1") (pin "4") (pinfunction "FIRQ_4") (pintype "input"))
      (node (ref "IC2") (pin "4") (pinfunction "FIRQ_4") (pintype "input"))
    )
    (net (code "84") (name "~{HALT}") (class "Default")
      (node (ref "IC1") (pin "40") (pinfunction "HALT_40") (pintype "input"))
      (node (ref "IC2") (pin "40") (pinfunction "HALT_40") (pintype "input"))
    )
    (net (code "85") (name "~{IRQ}") (class "Default")
      (node (ref "IC1") (pin "3") (pinfunction "IRQ_3") (pintype "input"))
      (node (ref "IC2") (pin "3") (pinfunction "IRQ_3") (pintype "input"))
    )
    (net (code "86") (name "~{NMI}") (class "Default")
      (node (ref "IC1") (pin "2") (pinfunction "NMI_2") (pintype "input"))
      (node (ref "IC2") (pin "2") (pinfunction "NMI_2") (pintype "input"))
    )
    (net (code "87") (name "~{RAM_WE}") (class "Default")
      (node (ref "IC3") (pin "74") (pinfunction "FB4MC11_74") (pintype "bidirectional"))
      (node (ref "IC5") (pin "29") (pinfunction "~{WE}_29") (pintype "input"))
    )
    (net (code "88") (name "~{RESET}") (class "Default")
      (node (ref "IC1") (pin "37") (pinfunction "RESET_37") (pintype "input"))
      (node (ref "IC2") (pin "37") (pinfunction "RESET_37") (pintype "input"))
      (node (ref "IC3") (pin "99") (pinfunction "FB2MC9-I/O/GSR_99") (pintype "bidirectional"))
    )
    (net (code "89") (name "~{TAG_OE}") (class "Default")
      (node (ref "IC3") (pin "16") (pinfunction "FB1MC1_16") (pintype "bidirectional"))
      (node (ref "IC6") (pin "22") (pinfunction "~{OE}_22") (pintype "input"))
    )
    (net (code "90") (name "~{TAG_WE}") (class "Default")
      (node (ref "IC3") (pin "4") (pinfunction "FB2MC11-I/O/GTS2_4") (pintype "bidirectional"))
      (node (ref "IC6") (pin "27") (pinfunction "~{WE}_27") (pintype "input"))
    )
  )
)
